# WS2811_Stepper.net
KiCad netlist of a schematic drawn in EAGLE
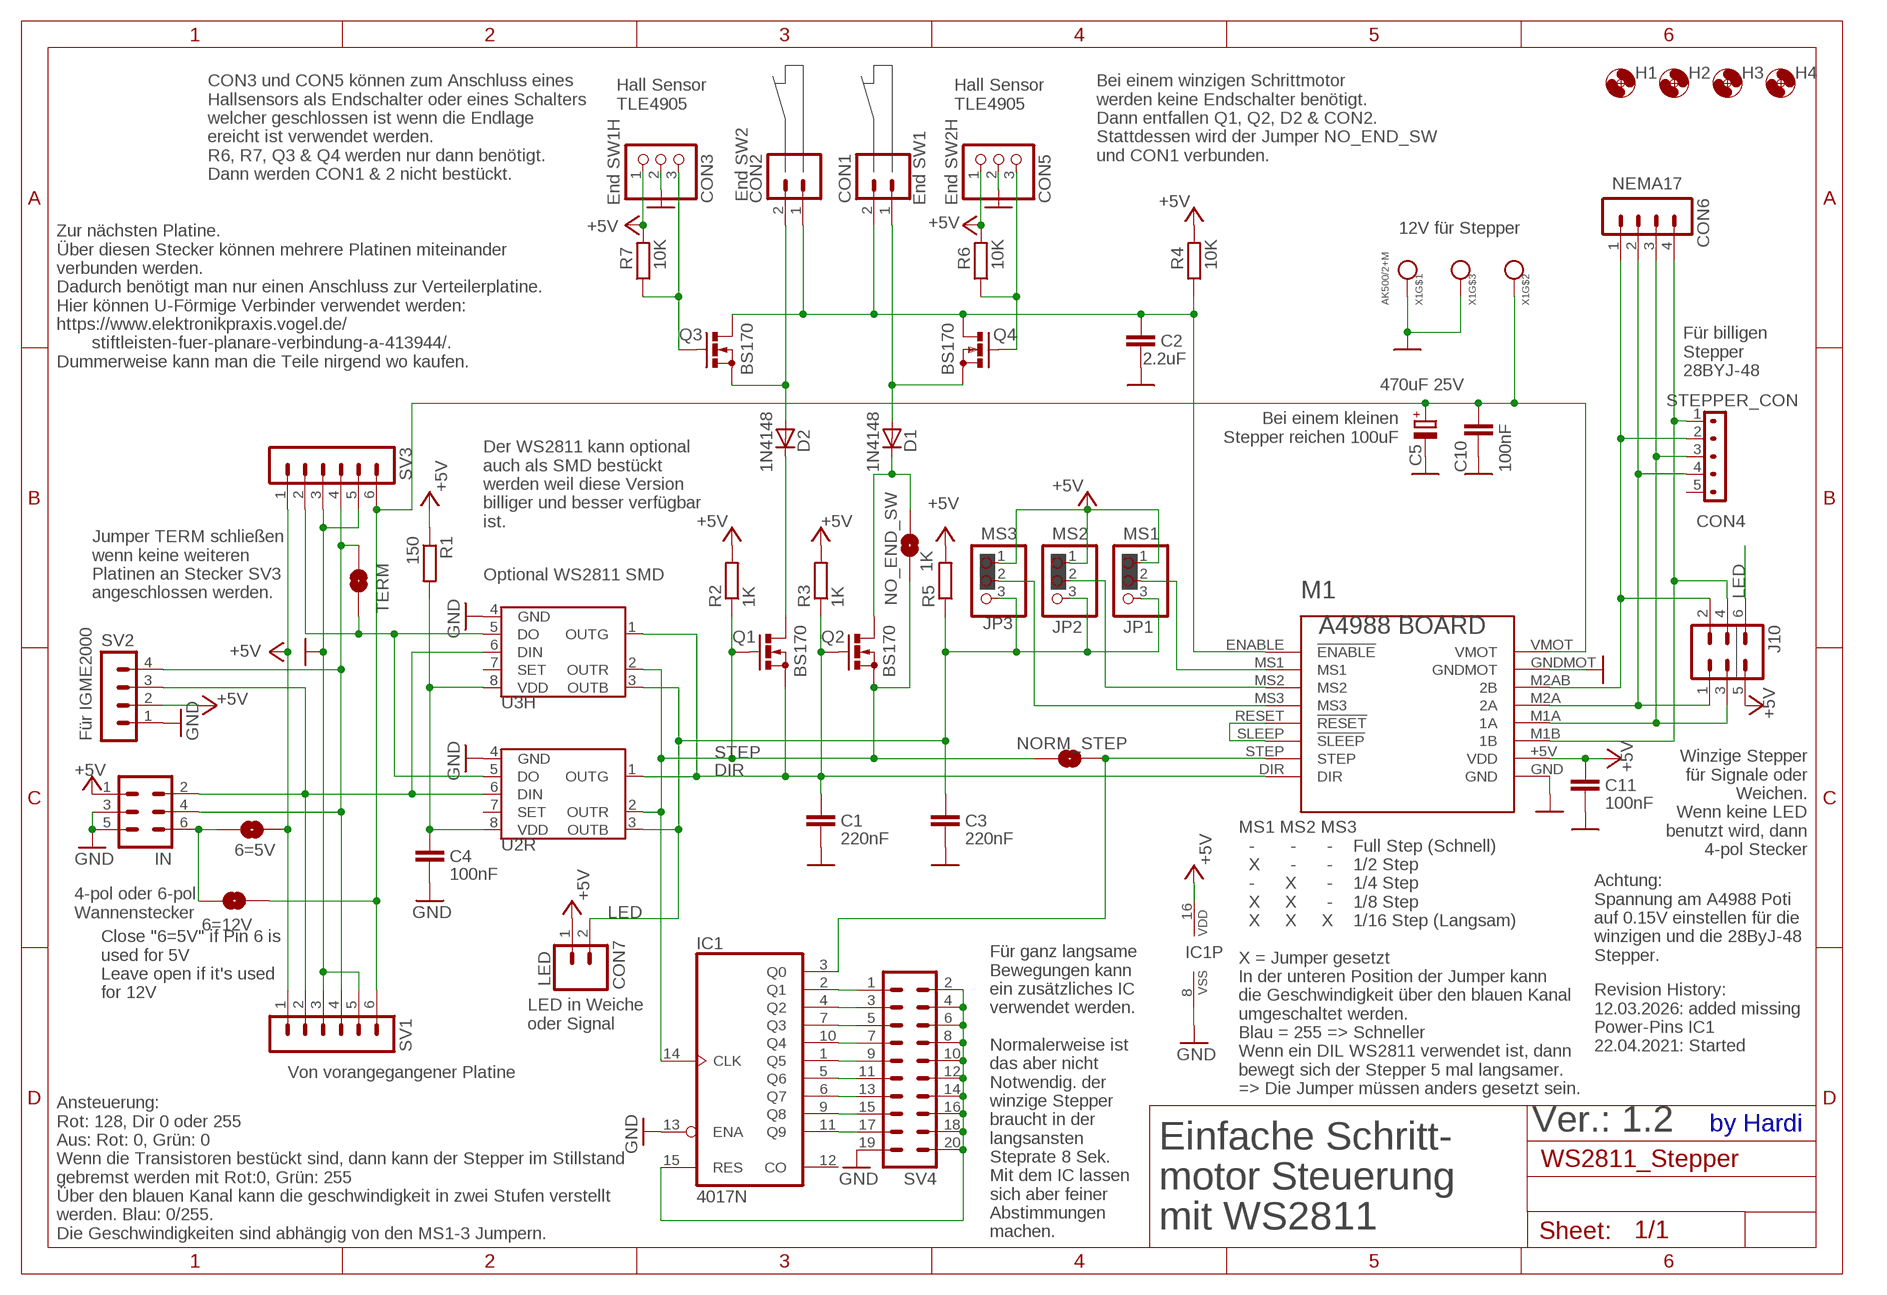
[diagram p0: schematic, sheet 1]

(export (version "E")
  (design (tool "Eeschema 10.0.6"))
  (components
    (comp (ref "6=5V")
      (value "SOLDERJUMPERNO")
      (footprint "eagle-import:SJ_2S-NO")
      (libsource (lib "eagle-import") (part "SOLDERJUMPERNO"))
    )
    (comp (ref "6=12V")
      (value "SOLDERJUMPERNO")
      (footprint "eagle-import:SJ_2S-NO")
      (libsource (lib "eagle-import") (part "SOLDERJUMPERNO"))
    )
    (comp (ref "C1")
      (value "220nF")
      (footprint "eagle-import:C050-024X044")
      (libsource (lib "eagle-import") (part "C-EU050-024X044"))
    )
    (comp (ref "C2")
      (value "2.2uF")
      (footprint "eagle-import:C050-024X044")
      (libsource (lib "eagle-import") (part "C-EU050-024X044"))
    )
    (comp (ref "C3")
      (value "220nF")
      (footprint "eagle-import:C050-024X044")
      (libsource (lib "eagle-import") (part "C-EU050-024X044"))
    )
    (comp (ref "C4")
      (value "100nF")
      (footprint "eagle-import:C050-024X044")
      (libsource (lib "eagle-import") (part "C-EU050-024X044"))
    )
    (comp (ref "C5")
      (value "470uF 25V")
      (footprint "eagle-import:E5-10,5")
      (libsource (lib "eagle-import") (part "CPOL-EUE5-10.5"))
    )
    (comp (ref "C10")
      (value "100nF")
      (footprint "eagle-import:C050-024X044")
      (libsource (lib "eagle-import") (part "C-EU050-024X044"))
    )
    (comp (ref "C11")
      (value "100nF")
      (footprint "eagle-import:C050-024X044")
      (libsource (lib "eagle-import") (part "C-EU050-024X044"))
    )
    (comp (ref "CON1")
      (value "End SW1")
      (footprint "eagle-import:1X02")
      (libsource (lib "eagle-import") (part "M02PTH"))
    )
    (comp (ref "CON2")
      (value "End SW2")
      (footprint "eagle-import:1X02")
      (libsource (lib "eagle-import") (part "M02PTH"))
    )
    (comp (ref "CON3")
      (value "End SW1H")
      (footprint "eagle-import:1X03-CLEANBIG")
      (libsource (lib "eagle-import") (part "PINHD-1X3CB"))
    )
    (comp (ref "CON4")
      (value "STEPPER_CON")
      (footprint "eagle-import:STEPPER_CON")
      (libsource (lib "eagle-import") (part "STEPPER_CON"))
    )
    (comp (ref "CON5")
      (value "End SW2H")
      (footprint "eagle-import:1X03-CLEANBIG")
      (libsource (lib "eagle-import") (part "PINHD-1X3CB"))
    )
    (comp (ref "CON6")
      (value "NEMA17")
      (footprint "eagle-import:MA04-1")
      (libsource (lib "eagle-import") (part "MA04-1"))
    )
    (comp (ref "CON7")
      (value "LED")
      (footprint "eagle-import:1X02")
      (libsource (lib "eagle-import") (part "M02PTH"))
    )
    (comp (ref "D1")
      (value "1N4148")
      (footprint "eagle-import:DO35-7")
      (libsource (lib "eagle-import") (part "1N4148DO35-7"))
    )
    (comp (ref "D2")
      (value "1N4148")
      (footprint "eagle-import:DO35-7")
      (libsource (lib "eagle-import") (part "1N4148DO35-7"))
    )
    (comp (ref "H1")
      (value "MOUNT-HOLE2.0")
      (footprint "eagle-import:2,0")
      (libsource (lib "eagle-import") (part "MOUNT-HOLE2.0"))
    )
    (comp (ref "H2")
      (value "MOUNT-HOLE2.0")
      (footprint "eagle-import:2,0")
      (libsource (lib "eagle-import") (part "MOUNT-HOLE2.0"))
    )
    (comp (ref "H3")
      (value "MOUNT-HOLE2.0")
      (footprint "eagle-import:2,0")
      (libsource (lib "eagle-import") (part "MOUNT-HOLE2.0"))
    )
    (comp (ref "H4")
      (value "MOUNT-HOLE2.0")
      (footprint "eagle-import:2,0")
      (libsource (lib "eagle-import") (part "MOUNT-HOLE2.0"))
    )
    (comp (ref "IC1")
      (value "4017N")
      (footprint "eagle-import:DIL16")
      (libsource (lib "eagle-import") (part "4017N"))
    )
    (comp (ref "IN")
      (value "ML6")
      (footprint "eagle-import:ML6")
      (libsource (lib "eagle-import") (part "ML6"))
    )
    (comp (ref "J10")
      (value "ML6")
      (footprint "eagle-import:ML6")
      (libsource (lib "eagle-import") (part "ML6"))
    )
    (comp (ref "JP1")
      (value "MS1")
      (footprint "eagle-import:1X03-CLEANBIG")
      (libsource (lib "eagle-import") (part "PINHD-1X3CB"))
    )
    (comp (ref "JP2")
      (value "MS2")
      (footprint "eagle-import:1X03-CLEANBIG")
      (libsource (lib "eagle-import") (part "PINHD-1X3CB"))
    )
    (comp (ref "JP3")
      (value "MS3")
      (footprint "eagle-import:1X03-CLEANBIG")
      (libsource (lib "eagle-import") (part "PINHD-1X3CB"))
    )
    (comp (ref "M1")
      (value "BOARD_A4988")
      (footprint "eagle-import:BOARD_A4988")
      (libsource (lib "eagle-import") (part "BOARD_A4988"))
    )
    (comp (ref "NORM_STEP")
      (value "SOLDERJUMPERNO")
      (footprint "eagle-import:SJ_2S-NO")
      (libsource (lib "eagle-import") (part "SOLDERJUMPERNO"))
    )
    (comp (ref "NO_END_SW")
      (value "SOLDERJUMPERNO")
      (footprint "eagle-import:SJ_2S-NO")
      (libsource (lib "eagle-import") (part "SOLDERJUMPERNO"))
    )
    (comp (ref "Q1")
      (value "BS170")
      (footprint "eagle-import:SOT54E")
      (libsource (lib "eagle-import") (part "BS170"))
    )
    (comp (ref "Q2")
      (value "BS170")
      (footprint "eagle-import:SOT54E")
      (libsource (lib "eagle-import") (part "BS170"))
    )
    (comp (ref "Q3")
      (value "BS170")
      (footprint "eagle-import:SOT54E")
      (libsource (lib "eagle-import") (part "BS170"))
    )
    (comp (ref "Q4")
      (value "BS170")
      (footprint "eagle-import:SOT54E")
      (libsource (lib "eagle-import") (part "BS170"))
    )
    (comp (ref "R1")
      (value "150")
      (footprint "eagle-import:RCL_0204_7")
      (libsource (lib "eagle-import") (part "RCL_R-EU_0204/7"))
    )
    (comp (ref "R2")
      (value "1K")
      (footprint "eagle-import:RCL_0204_7")
      (libsource (lib "eagle-import") (part "RCL_R-EU_0204/7"))
    )
    (comp (ref "R3")
      (value "1K")
      (footprint "eagle-import:RCL_0204_7")
      (libsource (lib "eagle-import") (part "RCL_R-EU_0204/7"))
    )
    (comp (ref "R4")
      (value "10K")
      (footprint "eagle-import:RCL_0204_7")
      (libsource (lib "eagle-import") (part "RCL_R-EU_0204/7"))
    )
    (comp (ref "R5")
      (value "1K")
      (footprint "eagle-import:RCL_0204_7")
      (libsource (lib "eagle-import") (part "RCL_R-EU_0204/7"))
    )
    (comp (ref "R6")
      (value "10K")
      (footprint "eagle-import:RCL_0204_7")
      (libsource (lib "eagle-import") (part "RCL_R-EU_0204/7"))
    )
    (comp (ref "R7")
      (value "10K")
      (footprint "eagle-import:RCL_0204_7")
      (libsource (lib "eagle-import") (part "RCL_R-EU_0204/7"))
    )
    (comp (ref "SV1")
      (value "MA06-1")
      (footprint "eagle-import:MA06-1")
      (libsource (lib "eagle-import") (part "MA06-1"))
    )
    (comp (ref "SV2")
      (value "MA04-1")
      (footprint "eagle-import:MA04-1")
      (libsource (lib "eagle-import") (part "MA04-1"))
    )
    (comp (ref "SV3")
      (value "MA06-1")
      (footprint "eagle-import:MA06-1")
      (libsource (lib "eagle-import") (part "MA06-1"))
    )
    (comp (ref "SV4")
      (value "MA10-2")
      (footprint "eagle-import:MA10-2")
      (libsource (lib "eagle-import") (part "MA10-2"))
    )
    (comp (ref "TERM")
      (value "SOLDERJUMPERNO")
      (footprint "eagle-import:SJ_2S-NO")
      (libsource (lib "eagle-import") (part "SOLDERJUMPERNO"))
    )
    (comp (ref "U2R")
      (value "WS2811")
      (footprint "eagle-import:S3PO_MODUL_WS2811_SOUND_MP3-TF-16P_WS2811_AND_ATTINY_WS2811_DIP08")
      (libsource (lib "eagle-import") (part "S3PO_MODUL_WS2811_SOUND_MP3-TF-16P_WS2811_AND_ATTINY_WS2811-ICTINY45-20-DIP"))
    )
    (comp (ref "U3H")
      (value "WS2811 SOT-8")
      (footprint "eagle-import:SOP8")
      (libsource (lib "eagle-import") (part "S3PO_MODUL_WS2811_SOUND_MP3-TF-16P_WS2811_AND_ATTINY_WS2811-ICSOP8"))
    )
    (comp (ref "X1")
      (value "AK500/2+M")
      (footprint "eagle-import:AK500_2+M")
      (libsource (lib "eagle-import") (part "AK500/2+M"))
    )
  )
  (nets
    (net (code "1") (name "+5V") (class "Default")
      (node (ref "6=5V") (pin "2") (pinfunction "2_2") (pintype "passive"))
      (node (ref "C11") (pin "1") (pinfunction "1_1") (pintype "passive"))
      (node (ref "CON3") (pin "1") (pinfunction "1_1") (pintype "passive"))
      (node (ref "CON5") (pin "1") (pinfunction "1_1") (pintype "passive"))
      (node (ref "CON7") (pin "1") (pinfunction "1_1") (pintype "passive"))
      (node (ref "IC1") (pin "16") (pinfunction "VDD_16") (pintype "power_in"))
      (node (ref "IN") (pin "1") (pinfunction "1_1") (pintype "passive"))
      (node (ref "J10") (pin "5") (pinfunction "5_5") (pintype "passive"))
      (node (ref "JP1") (pin "1") (pinfunction "1_1") (pintype "passive"))
      (node (ref "JP2") (pin "1") (pinfunction "1_1") (pintype "passive"))
      (node (ref "JP3") (pin "1") (pinfunction "1_1") (pintype "passive"))
      (node (ref "M1") (pin "+5V") (pinfunction "VDD_+5V") (pintype "power_in"))
      (node (ref "R1") (pin "1") (pinfunction "1_1") (pintype "passive"))
      (node (ref "R2") (pin "2") (pinfunction "2_2") (pintype "passive"))
      (node (ref "R3") (pin "2") (pinfunction "2_2") (pintype "passive"))
      (node (ref "R4") (pin "2") (pinfunction "2_2") (pintype "passive"))
      (node (ref "R5") (pin "2") (pinfunction "2_2") (pintype "passive"))
      (node (ref "R6") (pin "2") (pinfunction "2_2") (pintype "passive"))
      (node (ref "R7") (pin "2") (pinfunction "2_2") (pintype "passive"))
      (node (ref "SV1") (pin "1") (pinfunction "1_1") (pintype "passive"))
      (node (ref "SV2") (pin "2") (pinfunction "2_2") (pintype "passive"))
      (node (ref "SV3") (pin "1") (pinfunction "1_1") (pintype "passive"))
    )
    (net (code "2") (name "/DIR") (class "Default")
      (node (ref "C1") (pin "1") (pinfunction "1_1") (pintype "passive"))
      (node (ref "M1") (pin "DIR") (pinfunction "DIR_DIR") (pintype "input"))
      (node (ref "Q1") (pin "S") (pinfunction "S_S") (pintype "passive"))
      (node (ref "Q2") (pin "G") (pinfunction "G_G") (pintype "passive"))
      (node (ref "R3") (pin "1") (pinfunction "1_1") (pintype "passive"))
      (node (ref "U2R") (pin "1") (pinfunction "OUTG_1") (pintype "open_collector"))
      (node (ref "U3H") (pin "1") (pinfunction "OUTG_1") (pintype "open_collector"))
    )
    (net (code "3") (name "/LED") (class "Default")
      (node (ref "C3") (pin "1") (pinfunction "1_1") (pintype "passive"))
      (node (ref "CON7") (pin "2") (pinfunction "2_2") (pintype "passive"))
      (node (ref "J10") (pin "6") (pinfunction "6_6") (pintype "passive"))
      (node (ref "JP1") (pin "3") (pinfunction "3_3") (pintype "passive"))
      (node (ref "JP2") (pin "3") (pinfunction "3_3") (pintype "passive"))
      (node (ref "JP3") (pin "3") (pinfunction "3_3") (pintype "passive"))
      (node (ref "R5") (pin "1") (pinfunction "1_1") (pintype "passive"))
      (node (ref "U2R") (pin "3") (pinfunction "OUTB_3") (pintype "open_collector"))
      (node (ref "U3H") (pin "3") (pinfunction "OUTB_3") (pintype "open_collector"))
    )
    (net (code "4") (name "/STEP") (class "Default")
      (node (ref "IC1") (pin "14") (pinfunction "CLK_14") (pintype "input"))
      (node (ref "NORM_STEP") (pin "1") (pinfunction "1_1") (pintype "passive"))
      (node (ref "NO_END_SW") (pin "2") (pinfunction "2_2") (pintype "passive"))
      (node (ref "Q1") (pin "G") (pinfunction "G_G") (pintype "passive"))
      (node (ref "Q2") (pin "S") (pinfunction "S_S") (pintype "passive"))
      (node (ref "R2") (pin "1") (pinfunction "1_1") (pintype "passive"))
      (node (ref "U2R") (pin "2") (pinfunction "OUTR_2") (pintype "open_collector"))
      (node (ref "U3H") (pin "2") (pinfunction "OUTR_2") (pintype "open_collector"))
    )
    (net (code "5") (name "GND") (class "Default")
      (node (ref "C1") (pin "2") (pinfunction "2_2") (pintype "passive"))
      (node (ref "C10") (pin "2") (pinfunction "2_2") (pintype "passive"))
      (node (ref "C11") (pin "2") (pinfunction "2_2") (pintype "passive"))
      (node (ref "C2") (pin "2") (pinfunction "2_2") (pintype "passive"))
      (node (ref "C3") (pin "2") (pinfunction "2_2") (pintype "passive"))
      (node (ref "C4") (pin "2") (pinfunction "2_2") (pintype "passive"))
      (node (ref "C5") (pin "-") (pinfunction "-_-") (pintype "passive"))
      (node (ref "CON3") (pin "2") (pinfunction "2_2") (pintype "passive"))
      (node (ref "CON5") (pin "2") (pinfunction "2_2") (pintype "passive"))
      (node (ref "IC1") (pin "13") (pinfunction "ENA_13") (pintype "input"))
      (node (ref "IC1") (pin "8") (pinfunction "VSS_8") (pintype "power_in"))
      (node (ref "IN") (pin "3") (pinfunction "3_3") (pintype "passive"))
      (node (ref "IN") (pin "5") (pinfunction "5_5") (pintype "passive"))
      (node (ref "M1") (pin "GND") (pinfunction "GND_GND") (pintype "power_in"))
      (node (ref "M1") (pin "GNDMOT") (pinfunction "GNDMOT_GNDMOT") (pintype "power_in"))
      (node (ref "SV1") (pin "3") (pinfunction "3_3") (pintype "passive"))
      (node (ref "SV1") (pin "5") (pinfunction "5_5") (pintype "passive"))
      (node (ref "SV2") (pin "1") (pinfunction "1_1") (pintype "passive"))
      (node (ref "SV3") (pin "3") (pinfunction "3_3") (pintype "passive"))
      (node (ref "SV3") (pin "5") (pinfunction "5_5") (pintype "passive"))
      (node (ref "SV4") (pin "19") (pinfunction "19_19") (pintype "passive"))
      (node (ref "U2R") (pin "4") (pinfunction "GND_4") (pintype "power_in"))
      (node (ref "U3H") (pin "4") (pinfunction "GND_4") (pintype "power_in"))
      (node (ref "X1") (pin "1") (pinfunction "KL_1") (pintype "passive"))
      (node (ref "X1") (pin "M") (pinfunction "KL_M") (pintype "passive"))
    )
    (net (code "6") (name "Net-(6=12V-Pad2)") (class "Default")
      (node (ref "6=12V") (pin "2") (pinfunction "2_2") (pintype "passive"))
      (node (ref "6=5V") (pin "1") (pinfunction "1_1") (pintype "passive"))
      (node (ref "IN") (pin "6") (pinfunction "6_6") (pintype "passive"))
    )
    (net (code "7") (name "Net-(CON1-Pad1)") (class "Default")
      (node (ref "CON1") (pin "1") (pinfunction "1_1") (pintype "passive"))
      (node (ref "D1") (pin "A") (pinfunction "A_A") (pintype "passive"))
      (node (ref "Q4") (pin "S") (pinfunction "S_S") (pintype "passive"))
    )
    (net (code "8") (name "Net-(CON2-Pad2)") (class "Default")
      (node (ref "CON2") (pin "2") (pinfunction "2_2") (pintype "passive"))
      (node (ref "D2") (pin "A") (pinfunction "A_A") (pintype "passive"))
      (node (ref "Q3") (pin "S") (pinfunction "S_S") (pintype "passive"))
    )
    (net (code "9") (name "Net-(CON3-Pad3)") (class "Default")
      (node (ref "CON3") (pin "3") (pinfunction "3_3") (pintype "passive"))
      (node (ref "Q3") (pin "G") (pinfunction "G_G") (pintype "passive"))
      (node (ref "R7") (pin "1") (pinfunction "1_1") (pintype "passive"))
    )
    (net (code "10") (name "Net-(CON5-Pad3)") (class "Default")
      (node (ref "CON5") (pin "3") (pinfunction "3_3") (pintype "passive"))
      (node (ref "Q4") (pin "G") (pinfunction "G_G") (pintype "passive"))
      (node (ref "R6") (pin "1") (pinfunction "1_1") (pintype "passive"))
    )
    (net (code "11") (name "Net-(D1-PadC)") (class "Default")
      (node (ref "D1") (pin "C") (pinfunction "C_C") (pintype "passive"))
      (node (ref "NO_END_SW") (pin "1") (pinfunction "1_1") (pintype "passive"))
      (node (ref "Q2") (pin "D") (pinfunction "D_D") (pintype "passive"))
    )
    (net (code "12") (name "Net-(D2-PadC)") (class "Default")
      (node (ref "D2") (pin "C") (pinfunction "C_C") (pintype "passive"))
      (node (ref "Q1") (pin "D") (pinfunction "D_D") (pintype "passive"))
    )
    (net (code "13") (name "Net-(IC1A-Q0)") (class "Default")
      (node (ref "IC1") (pin "3") (pinfunction "Q0_3") (pintype "output"))
      (node (ref "M1") (pin "STEP") (pinfunction "STEP_STEP") (pintype "input"))
      (node (ref "NORM_STEP") (pin "2") (pinfunction "2_2") (pintype "passive"))
    )
    (net (code "14") (name "Net-(IC1A-Q1)") (class "Default")
      (node (ref "IC1") (pin "2") (pinfunction "Q1_2") (pintype "output"))
      (node (ref "SV4") (pin "1") (pinfunction "1_1") (pintype "passive"))
    )
    (net (code "15") (name "Net-(IC1A-Q2)") (class "Default")
      (node (ref "IC1") (pin "4") (pinfunction "Q2_4") (pintype "output"))
      (node (ref "SV4") (pin "3") (pinfunction "3_3") (pintype "passive"))
    )
    (net (code "16") (name "Net-(IC1A-Q3)") (class "Default")
      (node (ref "IC1") (pin "7") (pinfunction "Q3_7") (pintype "output"))
      (node (ref "SV4") (pin "5") (pinfunction "5_5") (pintype "passive"))
    )
    (net (code "17") (name "Net-(IC1A-Q4)") (class "Default")
      (node (ref "IC1") (pin "10") (pinfunction "Q4_10") (pintype "output"))
      (node (ref "SV4") (pin "7") (pinfunction "7_7") (pintype "passive"))
    )
    (net (code "18") (name "Net-(IC1A-Q5)") (class "Default")
      (node (ref "IC1") (pin "1") (pinfunction "Q5_1") (pintype "output"))
      (node (ref "SV4") (pin "9") (pinfunction "9_9") (pintype "passive"))
    )
    (net (code "19") (name "Net-(IC1A-Q6)") (class "Default")
      (node (ref "IC1") (pin "5") (pinfunction "Q6_5") (pintype "output"))
      (node (ref "SV4") (pin "11") (pinfunction "11_11") (pintype "passive"))
    )
    (net (code "20") (name "Net-(IC1A-Q7)") (class "Default")
      (node (ref "IC1") (pin "6") (pinfunction "Q7_6") (pintype "output"))
      (node (ref "SV4") (pin "13") (pinfunction "13_13") (pintype "passive"))
    )
    (net (code "21") (name "Net-(IC1A-Q8)") (class "Default")
      (node (ref "IC1") (pin "9") (pinfunction "Q8_9") (pintype "output"))
      (node (ref "SV4") (pin "15") (pinfunction "15_15") (pintype "passive"))
    )
    (net (code "22") (name "Net-(IC1A-Q9)") (class "Default")
      (node (ref "IC1") (pin "11") (pinfunction "Q9_11") (pintype "output"))
      (node (ref "SV4") (pin "17") (pinfunction "17_17") (pintype "passive"))
    )
    (net (code "23") (name "Net-(IC1A-RES)") (class "Default")
      (node (ref "IC1") (pin "15") (pinfunction "RES_15") (pintype "input"))
      (node (ref "SV4") (pin "10") (pinfunction "10_10") (pintype "passive"))
      (node (ref "SV4") (pin "12") (pinfunction "12_12") (pintype "passive"))
      (node (ref "SV4") (pin "14") (pinfunction "14_14") (pintype "passive"))
      (node (ref "SV4") (pin "16") (pinfunction "16_16") (pintype "passive"))
      (node (ref "SV4") (pin "18") (pinfunction "18_18") (pintype "passive"))
      (node (ref "SV4") (pin "2") (pinfunction "2_2") (pintype "passive"))
      (node (ref "SV4") (pin "20") (pinfunction "20_20") (pintype "passive"))
      (node (ref "SV4") (pin "4") (pinfunction "4_4") (pintype "passive"))
      (node (ref "SV4") (pin "6") (pinfunction "6_6") (pintype "passive"))
      (node (ref "SV4") (pin "8") (pinfunction "8_8") (pintype "passive"))
    )
    (net (code "24") (name "Net-(IN-Pad4)") (class "Default")
      (node (ref "IN") (pin "4") (pinfunction "4_4") (pintype "passive"))
      (node (ref "SV1") (pin "4") (pinfunction "4_4") (pintype "passive"))
      (node (ref "SV2") (pin "4") (pinfunction "4_4") (pintype "passive"))
      (node (ref "SV3") (pin "4") (pinfunction "4_4") (pintype "passive"))
      (node (ref "TERM") (pin "1") (pinfunction "1_1") (pintype "passive"))
    )
    (net (code "25") (name "Net-(JP1-Pad2)") (class "Default")
      (node (ref "JP1") (pin "2") (pinfunction "2_2") (pintype "passive"))
      (node (ref "M1") (pin "MS1") (pinfunction "MS1_MS1") (pintype "input"))
    )
    (net (code "26") (name "Net-(JP2-Pad2)") (class "Default")
      (node (ref "JP2") (pin "2") (pinfunction "2_2") (pintype "passive"))
      (node (ref "M1") (pin "MS2") (pinfunction "MS2_MS2") (pintype "input"))
    )
    (net (code "27") (name "Net-(JP3-Pad2)") (class "Default")
      (node (ref "JP3") (pin "2") (pinfunction "2_2") (pintype "passive"))
      (node (ref "M1") (pin "MS3") (pinfunction "MS3_MS3") (pintype "input"))
    )
    (net (code "28") (name "Net-(M1-1A)") (class "Default")
      (node (ref "CON4") (pin "3") (pinfunction "3_3") (pintype "passive"))
      (node (ref "CON6") (pin "3") (pinfunction "3_3") (pintype "passive"))
      (node (ref "J10") (pin "3") (pinfunction "3_3") (pintype "passive"))
      (node (ref "M1") (pin "M1A") (pinfunction "1A_M1A") (pintype "output"))
    )
    (net (code "29") (name "Net-(M1-1B)") (class "Default")
      (node (ref "CON4") (pin "1") (pinfunction "1_1") (pintype "passive"))
      (node (ref "CON6") (pin "4") (pinfunction "4_4") (pintype "passive"))
      (node (ref "J10") (pin "4") (pinfunction "4_4") (pintype "passive"))
      (node (ref "M1") (pin "M1B") (pinfunction "1B_M1B") (pintype "output"))
    )
    (net (code "30") (name "Net-(M1-2A)") (class "Default")
      (node (ref "CON4") (pin "4") (pinfunction "4_4") (pintype "passive"))
      (node (ref "CON6") (pin "2") (pinfunction "2_2") (pintype "passive"))
      (node (ref "J10") (pin "1") (pinfunction "1_1") (pintype "passive"))
      (node (ref "M1") (pin "M2A") (pinfunction "2A_M2A") (pintype "output"))
    )
    (net (code "31") (name "Net-(M1-2B)") (class "Default")
      (node (ref "CON4") (pin "2") (pinfunction "2_2") (pintype "passive"))
      (node (ref "CON6") (pin "1") (pinfunction "1_1") (pintype "passive"))
      (node (ref "J10") (pin "2") (pinfunction "2_2") (pintype "passive"))
      (node (ref "M1") (pin "M2AB") (pinfunction "2B_M2AB") (pintype "output"))
    )
    (net (code "32") (name "Net-(M1-~{ENABLE})") (class "Default")
      (node (ref "C2") (pin "1") (pinfunction "1_1") (pintype "passive"))
      (node (ref "CON1") (pin "2") (pinfunction "2_2") (pintype "passive"))
      (node (ref "CON2") (pin "1") (pinfunction "1_1") (pintype "passive"))
      (node (ref "M1") (pin "ENABLE") (pinfunction "~{ENABLE}_ENABLE") (pintype "input"))
      (node (ref "Q3") (pin "D") (pinfunction "D_D") (pintype "passive"))
      (node (ref "Q4") (pin "D") (pinfunction "D_D") (pintype "passive"))
      (node (ref "R4") (pin "1") (pinfunction "1_1") (pintype "passive"))
    )
    (net (code "33") (name "Net-(M1-~{RESET})") (class "Default")
      (node (ref "M1") (pin "RESET") (pinfunction "~{RESET}_RESET") (pintype "input"))
      (node (ref "M1") (pin "SLEEP") (pinfunction "~{SLEEP}_SLEEP") (pintype "input"))
    )
    (net (code "34") (name "Net-(U2R-DIN)") (class "Default")
      (node (ref "IN") (pin "2") (pinfunction "2_2") (pintype "passive"))
      (node (ref "SV1") (pin "2") (pinfunction "2_2") (pintype "passive"))
      (node (ref "SV2") (pin "3") (pinfunction "3_3") (pintype "passive"))
      (node (ref "U2R") (pin "6") (pinfunction "DIN_6") (pintype "input"))
      (node (ref "U3H") (pin "6") (pinfunction "DIN_6") (pintype "input"))
    )
    (net (code "35") (name "Net-(U2R-DO)") (class "Default")
      (node (ref "SV3") (pin "2") (pinfunction "2_2") (pintype "passive"))
      (node (ref "TERM") (pin "2") (pinfunction "2_2") (pintype "passive"))
      (node (ref "U2R") (pin "5") (pinfunction "DO_5") (pintype "output"))
      (node (ref "U3H") (pin "5") (pinfunction "DO_5") (pintype "output"))
    )
    (net (code "36") (name "Net-(U2R-VDD)") (class "Default")
      (node (ref "C4") (pin "1") (pinfunction "1_1") (pintype "passive"))
      (node (ref "R1") (pin "2") (pinfunction "2_2") (pintype "passive"))
      (node (ref "U2R") (pin "8") (pinfunction "VDD_8") (pintype "power_in"))
      (node (ref "U3H") (pin "8") (pinfunction "VDD_8") (pintype "power_in"))
    )
    (net (code "37") (name "Net-(X1B-KL)") (class "Default")
      (node (ref "6=12V") (pin "1") (pinfunction "1_1") (pintype "passive"))
      (node (ref "C10") (pin "1") (pinfunction "1_1") (pintype "passive"))
      (node (ref "C5") (pin "+") (pinfunction "+_+") (pintype "passive"))
      (node (ref "M1") (pin "VMOT") (pinfunction "VMOT_VMOT") (pintype "power_in"))
      (node (ref "SV1") (pin "6") (pinfunction "6_6") (pintype "passive"))
      (node (ref "SV3") (pin "6") (pinfunction "6_6") (pintype "passive"))
      (node (ref "X1") (pin "2") (pinfunction "KL_2") (pintype "passive"))
    )
    (net (code "38") (name "unconnected-(CON4-Pad5)") (class "Default")
      (node (ref "CON4") (pin "5") (pinfunction "5_5") (pintype "passive"))
    )
    (net (code "39") (name "unconnected-(IC1A-CO-Pad12)") (class "Default")
      (node (ref "IC1") (pin "12") (pinfunction "CO_12") (pintype "output"))
    )
    (net (code "40") (name "unconnected-(U2R-SET-Pad7)") (class "Default")
      (node (ref "U2R") (pin "7") (pinfunction "SET_7") (pintype "bidirectional"))
    )
    (net (code "41") (name "unconnected-(U3H-SET-Pad7)") (class "Default")
      (node (ref "U3H") (pin "7") (pinfunction "SET_7") (pintype "bidirectional"))
    )
  )
)
